# SCH-Orange_Pi_Power_Hat_EasyEDA.net
KiCad netlist of a schematic drawn in EasyEDA
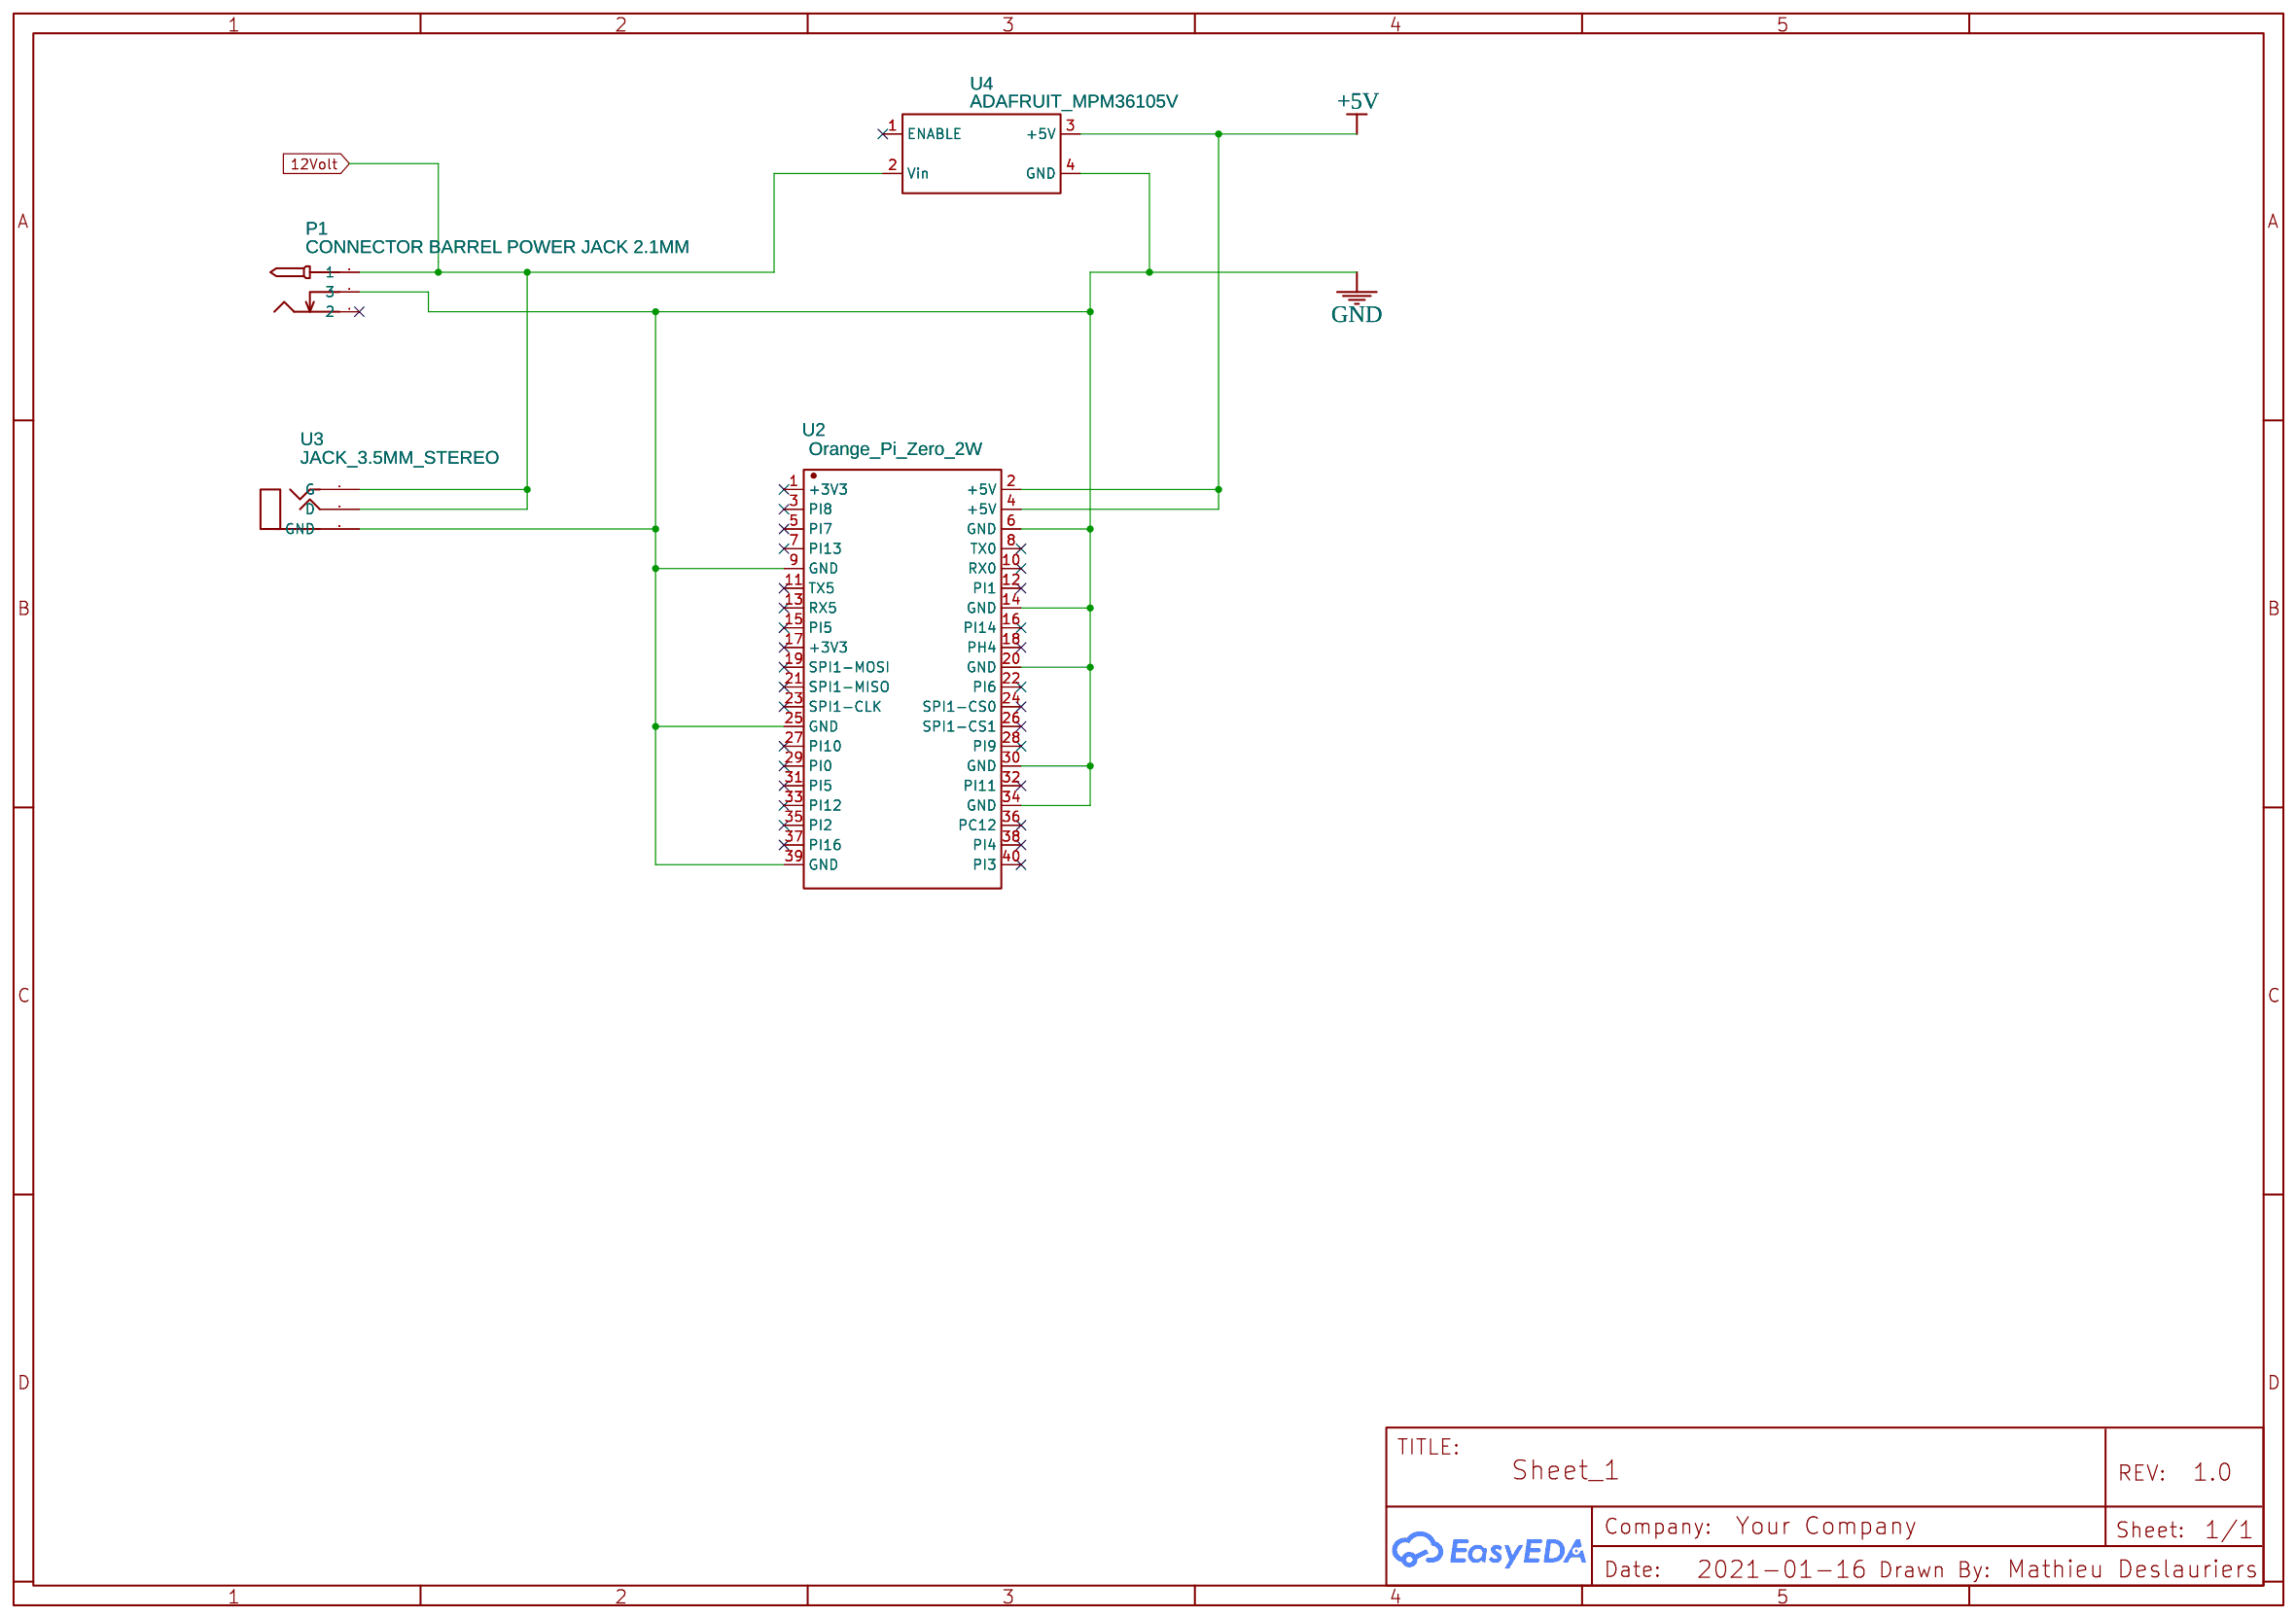
[diagram p0: schematic sheet]

(export (version "E")
  (design (tool "Eeschema 10.0.6"))
  (components
    (comp (ref "P1")
      (value "CONNECTOR BARREL POWER JACK 2.1MM")
      (libsource (lib "") (part "CONNECTOR BARREL POWER JACK 2.1MM"))
    )
    (comp (ref "U2")
      (value "Orange_Pi_Zero_2W")
      (fields (field (name "Manufacturer Part") "Raspberry Pi Zero W V1.3"))
      (libsource (lib "") (part "Raspberry_Pi_Zero_W"))
    )
    (comp (ref "U3")
      (value "JACK_3.5MM_STEREO")
      (fields (field (name "Manufacturer Part") "ST-029 AUDIO JACK 3.5mm"))
      (libsource (lib "") (part "JACK_3.5MM_STEREO"))
    )
    (comp (ref "U4") (value "ADAFRUIT_MPM36105V") (libsource (lib "") (part "ADAFRUIT_MPM36105V")))
  )
  (nets
    (net (code "1") (name "+5V") (class "Default")
      (node (ref "U2") (pin "2") (pinfunction "+5V_2") (pintype "passive"))
      (node (ref "U2") (pin "4") (pinfunction "+5V_4") (pintype "passive"))
      (node (ref "U4") (pin "3") (pinfunction "+5V_3") (pintype "unspecified"))
    )
    (net (code "2") (name "12Volt") (class "Default")
      (node (ref "P1") (pin "1") (pinfunction "1_1") (pintype "unspecified"))
      (node (ref "U3") (pin "1") (pinfunction "G_1") (pintype "unspecified"))
      (node (ref "U3") (pin "2") (pinfunction "D_2") (pintype "unspecified"))
      (node (ref "U4") (pin "2") (pinfunction "Vin_2") (pintype "unspecified"))
    )
    (net (code "3") (name "GND") (class "Default")
      (node (ref "P1") (pin "3") (pinfunction "3_3") (pintype "unspecified"))
      (node (ref "U2") (pin "14") (pinfunction "GND_14") (pintype "passive"))
      (node (ref "U2") (pin "20") (pinfunction "GND_20") (pintype "passive"))
      (node (ref "U2") (pin "25") (pinfunction "GND_25") (pintype "passive"))
      (node (ref "U2") (pin "30") (pinfunction "GND_30") (pintype "passive"))
      (node (ref "U2") (pin "34") (pinfunction "GND_34") (pintype "passive"))
      (node (ref "U2") (pin "39") (pinfunction "GND_39") (pintype "passive"))
      (node (ref "U2") (pin "6") (pinfunction "GND_6") (pintype "passive"))
      (node (ref "U2") (pin "9") (pinfunction "GND_9") (pintype "passive"))
      (node (ref "U3") (pin "3") (pinfunction "GND_3") (pintype "unspecified"))
      (node (ref "U4") (pin "4") (pinfunction "GND_4") (pintype "unspecified"))
    )
    (net (code "4") (name "unconnected-(P1-Pad2)") (class "Default")
      (node (ref "P1") (pin "2") (pinfunction "2_2") (pintype "unspecified+no_connect"))
    )
    (net (code "5") (name "unconnected-(U2-+3V3-Pad1)") (class "Default")
      (node (ref "U2") (pin "1") (pinfunction "+3V3_1") (pintype "passive+no_connect"))
    )
    (net (code "6") (name "unconnected-(U2-+3V3-Pad17)") (class "Default")
      (node (ref "U2") (pin "17") (pinfunction "+3V3_17") (pintype "passive+no_connect"))
    )
    (net (code "7") (name "unconnected-(U2-PC12-Pad36)") (class "Default")
      (node (ref "U2") (pin "36") (pinfunction "PC12_36") (pintype "bidirectional+no_connect"))
    )
    (net (code "8") (name "unconnected-(U2-PH4-Pad18)") (class "Default")
      (node (ref "U2") (pin "18") (pinfunction "PH4_18") (pintype "bidirectional+no_connect"))
    )
    (net (code "9") (name "unconnected-(U2-PI0-Pad29)") (class "Default")
      (node (ref "U2") (pin "29") (pinfunction "PI0_29") (pintype "bidirectional+no_connect"))
    )
    (net (code "10") (name "unconnected-(U2-PI1-Pad12)") (class "Default")
      (node (ref "U2") (pin "12") (pinfunction "PI1_12") (pintype "bidirectional+no_connect"))
    )
    (net (code "11") (name "unconnected-(U2-PI2-Pad35)") (class "Default")
      (node (ref "U2") (pin "35") (pinfunction "PI2_35") (pintype "bidirectional+no_connect"))
    )
    (net (code "12") (name "unconnected-(U2-PI3-Pad40)") (class "Default")
      (node (ref "U2") (pin "40") (pinfunction "PI3_40") (pintype "bidirectional+no_connect"))
    )
    (net (code "13") (name "unconnected-(U2-PI4-Pad38)") (class "Default")
      (node (ref "U2") (pin "38") (pinfunction "PI4_38") (pintype "bidirectional+no_connect"))
    )
    (net (code "14") (name "unconnected-(U2-PI5-Pad15)") (class "Default")
      (node (ref "U2") (pin "15") (pinfunction "PI5_15") (pintype "output+no_connect"))
    )
    (net (code "15") (name "unconnected-(U2-PI5-Pad31)") (class "Default")
      (node (ref "U2") (pin "31") (pinfunction "PI5_31") (pintype "bidirectional+no_connect"))
    )
    (net (code "16") (name "unconnected-(U2-PI6-Pad22)") (class "Default")
      (node (ref "U2") (pin "22") (pinfunction "PI6_22") (pintype "bidirectional+no_connect"))
    )
    (net (code "17") (name "unconnected-(U2-PI7-Pad5)") (class "Default")
      (node (ref "U2") (pin "5") (pinfunction "PI7_5") (pintype "bidirectional+no_connect"))
    )
    (net (code "18") (name "unconnected-(U2-PI8-Pad3)") (class "Default")
      (node (ref "U2") (pin "3") (pinfunction "PI8_3") (pintype "bidirectional+no_connect"))
    )
    (net (code "19") (name "unconnected-(U2-PI9-Pad28)") (class "Default")
      (node (ref "U2") (pin "28") (pinfunction "PI9_28") (pintype "unspecified+no_connect"))
    )
    (net (code "20") (name "unconnected-(U2-PI10-Pad27)") (class "Default")
      (node (ref "U2") (pin "27") (pinfunction "PI10_27") (pintype "unspecified+no_connect"))
    )
    (net (code "21") (name "unconnected-(U2-PI11-Pad32)") (class "Default")
      (node (ref "U2") (pin "32") (pinfunction "PI11_32") (pintype "bidirectional+no_connect"))
    )
    (net (code "22") (name "unconnected-(U2-PI12-Pad33)") (class "Default")
      (node (ref "U2") (pin "33") (pinfunction "PI12_33") (pintype "bidirectional+no_connect"))
    )
    (net (code "23") (name "unconnected-(U2-PI13-Pad7)") (class "Default")
      (node (ref "U2") (pin "7") (pinfunction "PI13_7") (pintype "bidirectional+no_connect"))
    )
    (net (code "24") (name "unconnected-(U2-PI14-Pad16)") (class "Default")
      (node (ref "U2") (pin "16") (pinfunction "PI14_16") (pintype "bidirectional+no_connect"))
    )
    (net (code "25") (name "unconnected-(U2-PI16-Pad37)") (class "Default")
      (node (ref "U2") (pin "37") (pinfunction "PI16_37") (pintype "bidirectional+no_connect"))
    )
    (net (code "26") (name "unconnected-(U2-RX0-Pad10)") (class "Default")
      (node (ref "U2") (pin "10") (pinfunction "RX0_10") (pintype "bidirectional+no_connect"))
    )
    (net (code "27") (name "unconnected-(U2-RX5-Pad13)") (class "Default")
      (node (ref "U2") (pin "13") (pinfunction "RX5_13") (pintype "bidirectional+no_connect"))
    )
    (net (code "28") (name "unconnected-(U2-SPI1-CLK-Pad23)") (class "Default")
      (node (ref "U2") (pin "23") (pinfunction "SPI1-CLK_23") (pintype "bidirectional+no_connect"))
    )
    (net (code "29") (name "unconnected-(U2-SPI1-CS0-Pad24)") (class "Default")
      (node (ref "U2") (pin "24") (pinfunction "SPI1-CS0_24") (pintype "bidirectional+no_connect"))
    )
    (net (code "30") (name "unconnected-(U2-SPI1-CS1-Pad26)") (class "Default")
      (node (ref "U2") (pin "26") (pinfunction "SPI1-CS1_26") (pintype "bidirectional+no_connect"))
    )
    (net (code "31") (name "unconnected-(U2-SPI1-MISO-Pad21)") (class "Default")
      (node (ref "U2") (pin "21") (pinfunction "SPI1-MISO_21") (pintype "bidirectional+no_connect"))
    )
    (net (code "32") (name "unconnected-(U2-SPI1-MOSI-Pad19)") (class "Default")
      (node (ref "U2") (pin "19") (pinfunction "SPI1-MOSI_19") (pintype "bidirectional+no_connect"))
    )
    (net (code "33") (name "unconnected-(U2-TX0-Pad8)") (class "Default")
      (node (ref "U2") (pin "8") (pinfunction "TX0_8") (pintype "passive+no_connect"))
    )
    (net (code "34") (name "unconnected-(U2-TX5-Pad11)") (class "Default")
      (node (ref "U2") (pin "11") (pinfunction "TX5_11") (pintype "bidirectional+no_connect"))
    )
    (net (code "35") (name "unconnected-(U4-ENABLE-Pad1)") (class "Default")
      (node (ref "U4") (pin "1") (pinfunction "ENABLE_1") (pintype "unspecified+no_connect"))
    )
  )
)
